# design.net
KiCad netlist of a schematic drawn in Altium Designer
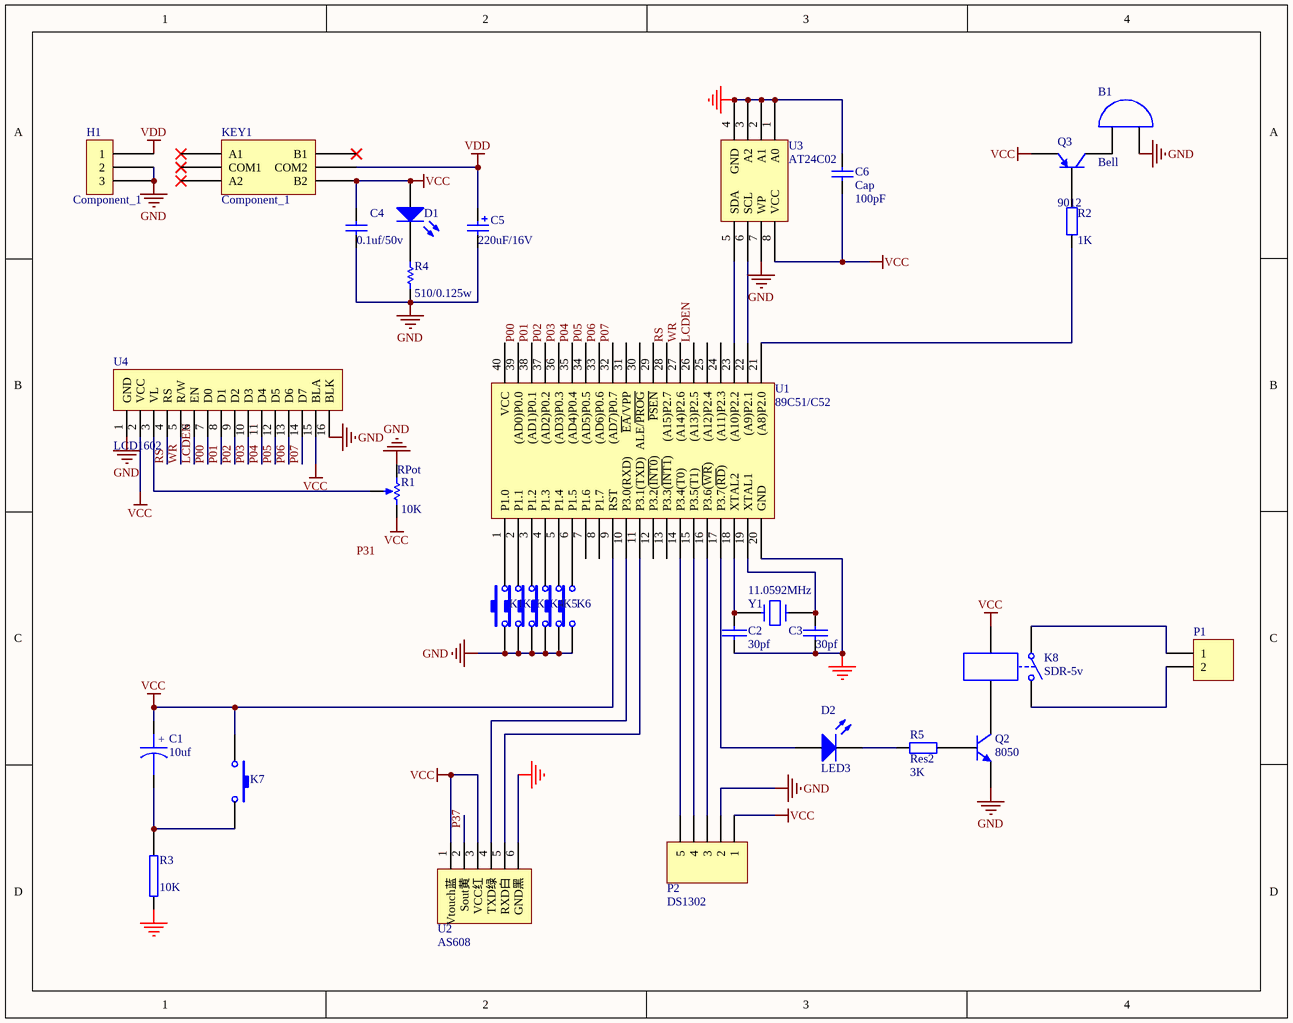
[diagram p0: 指纹锁原理图.schdoc]

(export (version "E")
  (design (tool "Eeschema 10.0.6"))
  (components
    (comp (ref "B1")
      (value "Bell")
      (footprint "PIN2")
      (description "Electrical Bell")
      (fields (field (name "PUBLISHER") "Altium Limited"))
      (libsource (lib "Miscellaneous Devices") (part "Bell"))
    )
    (comp (ref "C1")
      (value "10uf")
      (footprint "C0805")
      (description "Capacitor")
      (libsource (lib "*") (part "电解电容"))
    )
    (comp (ref "C2")
      (value "30pf")
      (footprint "C0805")
      (description "Capacitor")
      (libsource (lib "*") (part "CAP"))
    )
    (comp (ref "C3")
      (value "30pf")
      (footprint "C0805")
      (description "Capacitor")
      (libsource (lib "*") (part "CAP"))
    )
    (comp (ref "C4")
      (value "0.1uf/50v")
      (footprint "RAD-0.3")
      (description "Capacitor")
      (fields (field (name "Comment") "Cap") (field (name "PUBLISHER") "Altium Limited"))
      (libsource (lib "Miscellaneous Devices") (part "Cap"))
    )
    (comp (ref "C5")
      (value "220uF/16V")
      (footprint "Capacitor-Disk-Middle")
      (description "Polarized Capacitor (Axial)")
      (fields (field (name "Comment") "Cap Pol2") (field (name "PUBLISHER") "Altium Limited"))
      (libsource (lib "Miscellaneous Devices") (part "Cap Pol2"))
    )
    (comp (ref "C6")
      (value "Cap")
      (footprint "RAD-0.3")
      (description "Capacitor")
      (fields (field (name "ALTIUM_VALUE") "100pF") (field (name "PUBLISHER") "Altium Limited"))
      (libsource (lib "Miscellaneous Devices") (part "Cap"))
    )
    (comp (ref "D1")
      (value "LED Chip")
      (footprint "CLED1005-0402")
      (description "Typical Chip LED")
      (fields (field (name "PUBLISHER") "Altium Limited"))
      (libsource (lib "03-EButterflyIntegratedLibrary") (part "LED Chip"))
    )
    (comp (ref "D2")
      (value "LED3")
      (footprint "3.5X2.8X1.9")
      (description "Typical BLUE SiC LED")
      (fields (field (name "PUBLISHER") "Altium Limited"))
      (libsource (lib "Miscellaneous Devices") (part "LED3"))
    )
    (comp (ref "H1")
      (value "Component_1")
      (footprint "Miscellaneous Connectors:HDR1X3")
      (libsource (lib "DC电源") (part "Component_1"))
    )
    (comp (ref "K1")
      (value "Button")
      (footprint "BUTTON-DIP")
      (fields (field (name "PUBLISHER") "Altium Limited"))
      (libsource (lib "03-EButterflyIntegratedLibrary") (part "Button"))
    )
    (comp (ref "K2")
      (value "Button")
      (footprint "BUTTON-DIP")
      (fields (field (name "PUBLISHER") "Altium Limited"))
      (libsource (lib "03-EButterflyIntegratedLibrary") (part "Button"))
    )
    (comp (ref "K3")
      (value "Button")
      (footprint "BUTTON-DIP")
      (fields (field (name "PUBLISHER") "Altium Limited"))
      (libsource (lib "03-EButterflyIntegratedLibrary") (part "Button"))
    )
    (comp (ref "K4")
      (value "Button")
      (footprint "BUTTON-DIP")
      (fields (field (name "PUBLISHER") "Altium Limited"))
      (libsource (lib "03-EButterflyIntegratedLibrary") (part "Button"))
    )
    (comp (ref "K5")
      (value "Button")
      (footprint "BUTTON-DIP")
      (fields (field (name "PUBLISHER") "Altium Limited"))
      (libsource (lib "03-EButterflyIntegratedLibrary") (part "Button"))
    )
    (comp (ref "K6")
      (value "Button")
      (footprint "BUTTON-DIP")
      (fields (field (name "PUBLISHER") "Altium Limited"))
      (libsource (lib "03-EButterflyIntegratedLibrary") (part "Button"))
    )
    (comp (ref "K7")
      (value "Button")
      (footprint "BUTTON-DIP")
      (fields (field (name "PUBLISHER") "Altium Limited"))
      (libsource (lib "03-EButterflyIntegratedLibrary") (part "Button"))
    )
    (comp (ref "K8")
      (value "SDR-5v")
      (footprint "MODULE4")
      (description "Single-Pole Single-Throw Relay")
      (fields (field (name "PUBLISHER") "Altium Limited"))
      (libsource (lib "Miscellaneous Devices") (part "Relay-SPST"))
    )
    (comp (ref "KEY1")
      (value "Component_1")
      (footprint "HDR2X3")
      (libsource (lib "电源开关") (part "Component_1"))
    )
    (comp (ref "P1")
      (value "~")
      (footprint "MHDR1X2")
      (description "Header, 2-Pin")
      (fields (field (name "PUBLISHER") "Altium Limited"))
      (libsource (lib "Miscellaneous Connectors") (part "MHDR1X2"))
    )
    (comp (ref "P2")
      (value "DS1302")
      (footprint "MHDR1X5")
      (description "Header, 5-Pin")
      (fields (field (name "PUBLISHER") "Altium Limited"))
      (libsource (lib "Miscellaneous Connectors") (part "MHDR1X5"))
    )
    (comp (ref "Q2")
      (value "8050")
      (footprint "SOT-23B_N")
      (description "NPN Bipolar Transistor")
      (fields (field (name "PUBLISHER") "Altium Limited"))
      (libsource (lib "Miscellaneous Devices") (part "QNPN"))
    )
    (comp (ref "Q3")
      (value "9012")
      (footprint "TO-92A")
      (description "PNP General Purpose Amplifier")
      (fields (field (name "PUBLISHER") "Altium Limited"))
      (libsource (lib "Miscellaneous Devices") (part "2N3906"))
    )
    (comp (ref "R1")
      (value "RPot")
      (footprint "VR5")
      (description "Potentiometer")
      (fields (field (name "ALTIUM_VALUE") "10K") (field (name "PUBLISHER") "Altium Limited"))
      (libsource (lib "Miscellaneous Devices") (part "RPot"))
    )
    (comp (ref "R2")
      (value "1K")
      (footprint "AXIAL-0.4")
      (description "Resistor")
      (fields (field (name "PUBLISHER") "Altium Limited"))
      (libsource (lib "") (part "Res2_1"))
    )
    (comp (ref "R3") (value "10K") (footprint "RAD-0.1") (libsource (lib "*") (part "RES2")))
    (comp (ref "R4")
      (value "510/0.125w")
      (footprint "AXIAL-0.3")
      (description "Resistor")
      (fields (field (name "Comment") "Res1") (field (name "PUBLISHER") "Altium Limited"))
      (libsource (lib "Miscellaneous Devices") (part "Res1"))
    )
    (comp (ref "R5")
      (value "Res2")
      (footprint "AXIAL-0.4")
      (description "Resistor")
      (fields (field (name "ALTIUM_VALUE") "3K") (field (name "PUBLISHER") "Altium Limited"))
      (libsource (lib "Miscellaneous Devices") (part "Res2"))
    )
    (comp (ref "U1") (value "89C51/C52") (footprint "DIP-40") (libsource (lib "*") (part "AT89C51")))
    (comp (ref "U2") (value "AS608") (footprint "SIP-6") (libsource (lib "*") (part "FM608")))
    (comp (ref "U3") (value "AT24C02") (footprint "DIP8") (libsource (lib "*") (part "AT24C02")))
    (comp (ref "U4")
      (value "LCD1602")
      (footprint "LCD1602")
      (libsource (lib "02 Miscellaneous_Devices_ZSF_Library") (part "LCD1602"))
    )
    (comp (ref "Y1")
      (value "11.0592MHz")
      (footprint "XTAL-49/U_N")
      (description "Crystal")
      (libsource (lib "*") (part "CRYSTAL"))
    )
  )
  (nets
    (net (code "1") (name "/LCDEN") (class "Default")
      (node (ref "U1") (pin "26") (pinfunction "(A13)P2.5_26") (pintype "passive"))
      (node (ref "U4") (pin "6") (pinfunction "EN_6") (pintype "passive"))
    )
    (net (code "2") (name "/P00") (class "Default")
      (node (ref "U1") (pin "39") (pinfunction "(AD0)P0.0_39") (pintype "passive"))
      (node (ref "U4") (pin "7") (pinfunction "D0_7") (pintype "passive"))
    )
    (net (code "3") (name "/P01") (class "Default")
      (node (ref "U1") (pin "38") (pinfunction "(AD1)P0.1_38") (pintype "passive"))
      (node (ref "U4") (pin "8") (pinfunction "D1_8") (pintype "passive"))
    )
    (net (code "4") (name "/P02") (class "Default")
      (node (ref "U1") (pin "37") (pinfunction "(AD2)P0.2_37") (pintype "passive"))
      (node (ref "U4") (pin "9") (pinfunction "D2_9") (pintype "passive"))
    )
    (net (code "5") (name "/P03") (class "Default")
      (node (ref "U1") (pin "36") (pinfunction "(AD3)P0.3_36") (pintype "passive"))
      (node (ref "U4") (pin "10") (pinfunction "D3_10") (pintype "passive"))
    )
    (net (code "6") (name "/P04") (class "Default")
      (node (ref "U1") (pin "35") (pinfunction "(AD4)P0.4_35") (pintype "passive"))
      (node (ref "U4") (pin "11") (pinfunction "D4_11") (pintype "passive"))
    )
    (net (code "7") (name "/P05") (class "Default")
      (node (ref "U1") (pin "34") (pinfunction "(AD5)P0.5_34") (pintype "passive"))
      (node (ref "U4") (pin "12") (pinfunction "D5_12") (pintype "passive"))
    )
    (net (code "8") (name "/P06") (class "Default")
      (node (ref "U1") (pin "33") (pinfunction "(AD6)P0.6_33") (pintype "passive"))
      (node (ref "U4") (pin "13") (pinfunction "D6_13") (pintype "passive"))
    )
    (net (code "9") (name "/P07") (class "Default")
      (node (ref "U1") (pin "32") (pinfunction "(AD7)P0.7_32") (pintype "passive"))
      (node (ref "U4") (pin "14") (pinfunction "D7_14") (pintype "passive"))
    )
    (net (code "11") (name "/P37") (class "Default")
      (node (ref "U2") (pin "2") (pinfunction "Sout黄_2") (pintype "passive"))
    )
    (net (code "12") (name "/RS") (class "Default")
      (node (ref "U1") (pin "28") (pinfunction "(A15)P2.7_28") (pintype "passive"))
      (node (ref "U4") (pin "4") (pinfunction "RS_4") (pintype "passive"))
    )
    (net (code "13") (name "/WR") (class "Default")
      (node (ref "U1") (pin "27") (pinfunction "(A14)P2.6_27") (pintype "passive"))
      (node (ref "U4") (pin "5") (pinfunction "R/W_5") (pintype "passive"))
    )
    (net (code "14") (name "GND") (class "Default")
      (node (ref "B1") (pin "2") (pinfunction "B_2") (pintype "passive"))
      (node (ref "C2") (pin "2") (pinfunction "2_2") (pintype "passive"))
      (node (ref "C3") (pin "2") (pinfunction "2_2") (pintype "passive"))
      (node (ref "C4") (pin "1") (pinfunction "1_1") (pintype "passive"))
      (node (ref "C5") (pin "2") (pinfunction "2_2") (pintype "passive"))
      (node (ref "C6") (pin "2") (pinfunction "2_2") (pintype "passive"))
      (node (ref "H1") (pin "2") (pinfunction "2_2") (pintype "passive"))
      (node (ref "H1") (pin "3") (pinfunction "3_3") (pintype "passive"))
      (node (ref "K1") (pin "2") (pinfunction "2_2") (pintype "passive"))
      (node (ref "K2") (pin "2") (pinfunction "2_2") (pintype "passive"))
      (node (ref "K3") (pin "2") (pinfunction "2_2") (pintype "passive"))
      (node (ref "K4") (pin "2") (pinfunction "2_2") (pintype "passive"))
      (node (ref "K5") (pin "2") (pinfunction "2_2") (pintype "passive"))
      (node (ref "K6") (pin "2") (pinfunction "2_2") (pintype "passive"))
      (node (ref "P2") (pin "2") (pinfunction "2_2") (pintype "passive"))
      (node (ref "Q2") (pin "3") (pinfunction "E_3") (pintype "passive"))
      (node (ref "R1") (pin "1") (pinfunction "TOP_1") (pintype "passive"))
      (node (ref "R4") (pin "1") (pinfunction "1_1") (pintype "passive"))
      (node (ref "U1") (pin "20") (pinfunction "GND_20") (pintype "passive"))
      (node (ref "U2") (pin "6") (pinfunction "GND黑_6") (pintype "passive"))
      (node (ref "U3") (pin "1") (pinfunction "A0_1") (pintype "passive"))
      (node (ref "U3") (pin "2") (pinfunction "A1_2") (pintype "passive"))
      (node (ref "U3") (pin "3") (pinfunction "A2_3") (pintype "passive"))
      (node (ref "U3") (pin "4") (pinfunction "GND_4") (pintype "passive"))
      (node (ref "U3") (pin "7") (pinfunction "WP_7") (pintype "passive"))
      (node (ref "U4") (pin "1") (pinfunction "GND_1") (pintype "passive"))
      (node (ref "U4") (pin "16") (pinfunction "BLK_16") (pintype "passive"))
    )
    (net (code "15") (name "Net-(B1-A)") (class "Default")
      (node (ref "B1") (pin "1") (pinfunction "A_1") (pintype "passive"))
      (node (ref "Q3") (pin "3") (pinfunction "C_3") (pintype "passive"))
    )
    (net (code "16") (name "Net-(C1-Pad1)") (class "Default")
      (node (ref "C1") (pin "1") (pinfunction "1_1") (pintype "passive"))
      (node (ref "K7") (pin "1") (pinfunction "1_1") (pintype "passive"))
      (node (ref "R3") (pin "2") (pinfunction "2_2") (pintype "passive"))
    )
    (net (code "17") (name "Net-(D1-K)") (class "Default")
      (node (ref "D1") (pin "2") (pinfunction "K_2") (pintype "passive"))
      (node (ref "R4") (pin "2") (pinfunction "2_2") (pintype "passive"))
    )
    (net (code "18") (name "Net-(D2-A)") (class "Default")
      (node (ref "D2") (pin "1") (pinfunction "A_1") (pintype "passive"))
      (node (ref "U1") (pin "17") (pinfunction "P3.7(~{RD})_17") (pintype "passive"))
    )
    (net (code "19") (name "Net-(D2-K)") (class "Default")
      (node (ref "D2") (pin "2") (pinfunction "K_2") (pintype "passive"))
      (node (ref "R5") (pin "1") (pinfunction "1_1") (pintype "passive"))
    )
    (net (code "20") (name "Net-(K8-Pad1)") (class "Default")
      (node (ref "K8") (pin "1") (pinfunction "1_1") (pintype "passive"))
      (node (ref "P1") (pin "1") (pinfunction "1_1") (pintype "passive"))
    )
    (net (code "21") (name "Net-(K8-Pad2)") (class "Default")
      (node (ref "K8") (pin "2") (pinfunction "2_2") (pintype "passive"))
      (node (ref "P1") (pin "2") (pinfunction "2_2") (pintype "passive"))
    )
    (net (code "22") (name "Net-(Q2-B)") (class "Default")
      (node (ref "Q2") (pin "2") (pinfunction "B_2") (pintype "passive"))
      (node (ref "R5") (pin "2") (pinfunction "2_2") (pintype "passive"))
    )
    (net (code "23") (name "Net-(Q2-C)") (class "Default")
      (node (ref "K8") (pin "4") (pinfunction "4_4") (pintype "passive"))
      (node (ref "Q2") (pin "1") (pinfunction "C_1") (pintype "passive"))
    )
    (net (code "24") (name "Net-(Q3-B)") (class "Default")
      (node (ref "Q3") (pin "2") (pinfunction "B_2") (pintype "passive"))
      (node (ref "R2") (pin "2") (pinfunction "2_2") (pintype "passive"))
    )
    (net (code "25") (name "Net-(R1-TAP)") (class "Default")
      (node (ref "R1") (pin "3") (pinfunction "TAP_3") (pintype "passive"))
      (node (ref "U4") (pin "3") (pinfunction "VL_3") (pintype "passive"))
    )
    (net (code "26") (name "Net-(U1-(A8)P2.0)") (class "Default")
      (node (ref "R2") (pin "1") (pinfunction "1_1") (pintype "passive"))
      (node (ref "U1") (pin "21") (pinfunction "(A8)P2.0_21") (pintype "passive"))
    )
    (net (code "27") (name "Net-(U1-(A9)P2.1)") (class "Default")
      (node (ref "U1") (pin "22") (pinfunction "(A9)P2.1_22") (pintype "passive"))
      (node (ref "U3") (pin "6") (pinfunction "SCL_6") (pintype "passive"))
    )
    (net (code "28") (name "Net-(U1-(A10)P2.2)") (class "Default")
      (node (ref "U1") (pin "23") (pinfunction "(A10)P2.2_23") (pintype "passive"))
      (node (ref "U3") (pin "5") (pinfunction "SDA_5") (pintype "passive"))
    )
    (net (code "29") (name "Net-(U1-P1.0)") (class "Default")
      (node (ref "K1") (pin "1") (pinfunction "1_1") (pintype "passive"))
      (node (ref "U1") (pin "1") (pinfunction "P1.0_1") (pintype "passive"))
    )
    (net (code "30") (name "Net-(U1-P1.1)") (class "Default")
      (node (ref "K2") (pin "1") (pinfunction "1_1") (pintype "passive"))
      (node (ref "U1") (pin "2") (pinfunction "P1.1_2") (pintype "passive"))
    )
    (net (code "31") (name "Net-(U1-P1.2)") (class "Default")
      (node (ref "K3") (pin "1") (pinfunction "1_1") (pintype "passive"))
      (node (ref "U1") (pin "3") (pinfunction "P1.2_3") (pintype "passive"))
    )
    (net (code "32") (name "Net-(U1-P1.3)") (class "Default")
      (node (ref "K4") (pin "1") (pinfunction "1_1") (pintype "passive"))
      (node (ref "U1") (pin "4") (pinfunction "P1.3_4") (pintype "passive"))
    )
    (net (code "33") (name "Net-(U1-P1.4)") (class "Default")
      (node (ref "K5") (pin "1") (pinfunction "1_1") (pintype "passive"))
      (node (ref "U1") (pin "5") (pinfunction "P1.4_5") (pintype "passive"))
    )
    (net (code "34") (name "Net-(U1-P1.5)") (class "Default")
      (node (ref "K6") (pin "1") (pinfunction "1_1") (pintype "passive"))
      (node (ref "U1") (pin "6") (pinfunction "P1.5_6") (pintype "passive"))
    )
    (net (code "35") (name "Net-(U1-P3.0(RXD))") (class "Default")
      (node (ref "U1") (pin "10") (pinfunction "P3.0(RXD)_10") (pintype "passive"))
      (node (ref "U2") (pin "4") (pinfunction "TXD绿_4") (pintype "passive"))
    )
    (net (code "36") (name "Net-(U1-P3.1(TXD))") (class "Default")
      (node (ref "U1") (pin "11") (pinfunction "P3.1(TXD)_11") (pintype "passive"))
      (node (ref "U2") (pin "5") (pinfunction "RXD白_5") (pintype "passive"))
    )
    (net (code "37") (name "Net-(U1-P3.4(T0))") (class "Default")
      (node (ref "P2") (pin "5") (pinfunction "5_5") (pintype "passive"))
      (node (ref "U1") (pin "14") (pinfunction "P3.4(T0)_14") (pintype "passive"))
    )
    (net (code "38") (name "Net-(U1-P3.5(T1))") (class "Default")
      (node (ref "P2") (pin "4") (pinfunction "4_4") (pintype "passive"))
      (node (ref "U1") (pin "15") (pinfunction "P3.5(T1)_15") (pintype "passive"))
    )
    (net (code "39") (name "Net-(U1-P3.6(~{WR}))") (class "Default")
      (node (ref "P2") (pin "3") (pinfunction "3_3") (pintype "passive"))
      (node (ref "U1") (pin "16") (pinfunction "P3.6(~{WR})_16") (pintype "passive"))
    )
    (net (code "40") (name "Net-(U1-XTAL1)") (class "Default")
      (node (ref "C3") (pin "1") (pinfunction "1_1") (pintype "passive"))
      (node (ref "U1") (pin "19") (pinfunction "XTAL1_19") (pintype "passive"))
      (node (ref "Y1") (pin "2") (pinfunction "2_2") (pintype "passive"))
    )
    (net (code "41") (name "Net-(U1-XTAL2)") (class "Default")
      (node (ref "C2") (pin "1") (pinfunction "1_1") (pintype "passive"))
      (node (ref "U1") (pin "18") (pinfunction "XTAL2_18") (pintype "passive"))
      (node (ref "Y1") (pin "1") (pinfunction "1_1") (pintype "passive"))
    )
    (net (code "42") (name "VCC") (class "Default")
      (node (ref "C1") (pin "2") (pinfunction "2_2") (pintype "passive"))
      (node (ref "C4") (pin "2") (pinfunction "2_2") (pintype "passive"))
      (node (ref "C6") (pin "1") (pinfunction "1_1") (pintype "passive"))
      (node (ref "D1") (pin "1") (pinfunction "A_1") (pintype "passive"))
      (node (ref "K7") (pin "2") (pinfunction "2_2") (pintype "passive"))
      (node (ref "K8") (pin "3") (pinfunction "3_3") (pintype "passive"))
      (node (ref "KEY1") (pin "6") (pinfunction "B2_6") (pintype "passive"))
      (node (ref "P2") (pin "1") (pinfunction "1_1") (pintype "passive"))
      (node (ref "Q3") (pin "1") (pinfunction "E_1") (pintype "passive"))
      (node (ref "R1") (pin "2") (pinfunction "BOT_2") (pintype "passive"))
      (node (ref "U1") (pin "9") (pinfunction "RST_9") (pintype "passive"))
      (node (ref "U2") (pin "1") (pinfunction "Vtouch蓝_1") (pintype "passive"))
      (node (ref "U2") (pin "3") (pinfunction "VCC红_3") (pintype "passive"))
      (node (ref "U3") (pin "8") (pinfunction "VCC_8") (pintype "passive"))
      (node (ref "U4") (pin "15") (pinfunction "BLA_15") (pintype "passive"))
      (node (ref "U4") (pin "2") (pinfunction "VCC_2") (pintype "passive"))
    )
    (net (code "43") (name "VDD") (class "Default")
      (node (ref "C5") (pin "1") (pinfunction "1_1") (pintype "passive"))
      (node (ref "H1") (pin "1") (pinfunction "1_1") (pintype "passive"))
      (node (ref "KEY1") (pin "5") (pinfunction "COM2_5") (pintype "passive"))
    )
    (net (code "44") (name "unconnected-(KEY1-A1-Pad1)") (class "Default")
      (node (ref "KEY1") (pin "1") (pinfunction "A1_1") (pintype "passive+no_connect"))
    )
    (net (code "45") (name "unconnected-(KEY1-A2-Pad3)") (class "Default")
      (node (ref "KEY1") (pin "3") (pinfunction "A2_3") (pintype "passive+no_connect"))
    )
    (net (code "46") (name "unconnected-(KEY1-B1-Pad4)") (class "Default")
      (node (ref "KEY1") (pin "4") (pinfunction "B1_4") (pintype "passive+no_connect"))
    )
    (net (code "47") (name "unconnected-(KEY1-COM1-Pad2)") (class "Default")
      (node (ref "KEY1") (pin "2") (pinfunction "COM1_2") (pintype "passive+no_connect"))
    )
    (net (code "48") (name "unconnected-(R3-Pad1)") (class "Default")
      (node (ref "R3") (pin "1") (pinfunction "1_1") (pintype "passive"))
    )
    (net (code "49") (name "unconnected-(U1-(A11)P2.3-Pad24)") (class "Default")
      (node (ref "U1") (pin "24") (pinfunction "(A11)P2.3_24") (pintype "passive"))
    )
    (net (code "50") (name "unconnected-(U1-(A12)P2.4-Pad25)") (class "Default")
      (node (ref "U1") (pin "25") (pinfunction "(A12)P2.4_25") (pintype "passive"))
    )
    (net (code "51") (name "unconnected-(U1-ALE{slash}~{PROG}-Pad30)") (class "Default")
      (node (ref "U1") (pin "30") (pinfunction "ALE/~{PROG}_30") (pintype "passive"))
    )
    (net (code "52") (name "unconnected-(U1-P1.6-Pad7)") (class "Default")
      (node (ref "U1") (pin "7") (pinfunction "P1.6_7") (pintype "passive"))
    )
    (net (code "53") (name "unconnected-(U1-P1.7-Pad8)") (class "Default")
      (node (ref "U1") (pin "8") (pinfunction "P1.7_8") (pintype "passive"))
    )
    (net (code "54") (name "unconnected-(U1-P3.2(~{INT0})-Pad12)") (class "Default")
      (node (ref "U1") (pin "12") (pinfunction "P3.2(~{INT0})_12") (pintype "passive"))
    )
    (net (code "55") (name "unconnected-(U1-P3.3(~{INT1})-Pad13)") (class "Default")
      (node (ref "U1") (pin "13") (pinfunction "P3.3(~{INT1})_13") (pintype "passive"))
    )
    (net (code "56") (name "unconnected-(U1-VCC-Pad40)") (class "Default")
      (node (ref "U1") (pin "40") (pinfunction "VCC_40") (pintype "passive"))
    )
    (net (code "57") (name "unconnected-(U1-~{EA}{slash}VPP-Pad31)") (class "Default")
      (node (ref "U1") (pin "31") (pinfunction "~{EA}/VPP_31") (pintype "passive"))
    )
    (net (code "58") (name "unconnected-(U1-~{PSEN}-Pad29)") (class "Default")
      (node (ref "U1") (pin "29") (pinfunction "~{PSEN}_29") (pintype "passive"))
    )
  )
)
